# Top.net
KiCad netlist of a schematic drawn in Altium Designer
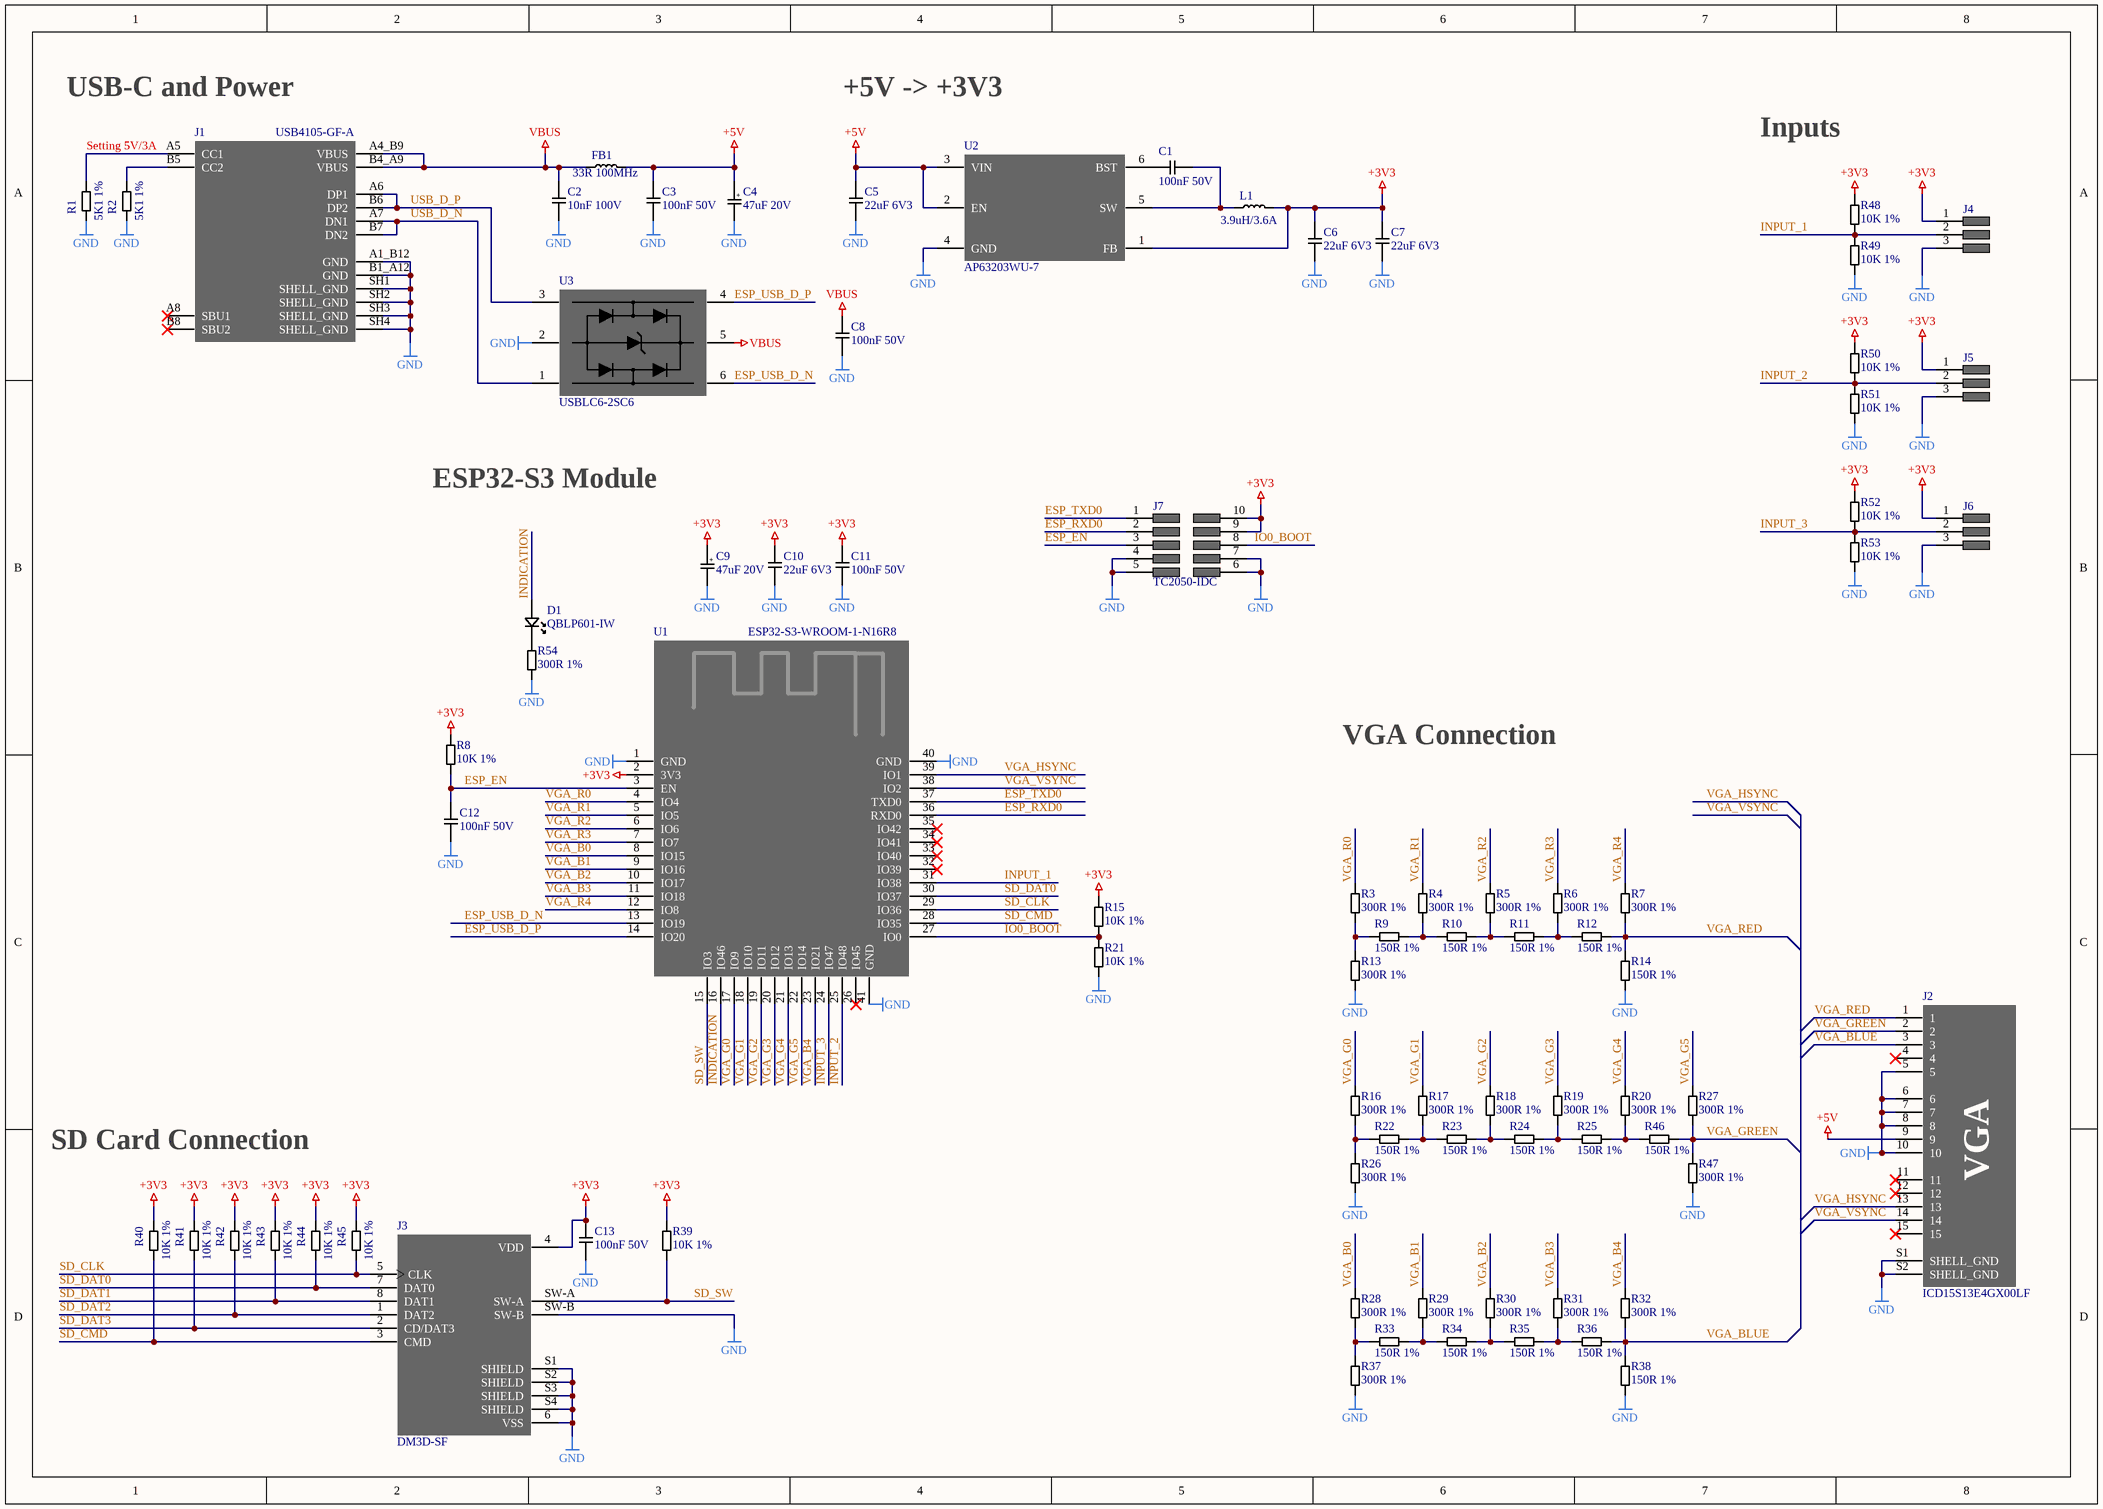
[diagram p0: Top.SchDoc]

(export (version "E")
  (design (tool "Eeschema 10.0.6"))
  (components
    (comp (ref "C1")
      (value "100nF 50V")
      (footprint "CAPC1608X06N")
      (description "0.1 µF ±10% 50V Ceramic Capacitor X7R 0603 (1608 Metric)")
      (fields (field (name "MPN") "GCM188R71H104KA57D"))
      (libsource (lib "VESA-ESP_LIB") (part "100nF 50V"))
    )
    (comp (ref "C2")
      (value "10nF 100V")
      (footprint "CAPC1608X06N")
      (description "10000 pF ±10% 100V Ceramic Capacitor X7R 0603 (1608 Metric)")
      (fields (field (name "MPN") "GCM188R72A103KA37D"))
      (libsource (lib "VESA-ESP_LIB") (part "10nF 100V"))
    )
    (comp (ref "C3")
      (value "100nF 50V")
      (footprint "CAPC1608X06N")
      (description "0.1 µF ±10% 50V Ceramic Capacitor X7R 0603 (1608 Metric)")
      (fields (field (name "MPN") "GCM188R71H104KA57D"))
      (libsource (lib "VESA-ESP_LIB") (part "100nF 50V"))
    )
    (comp (ref "C4")
      (value "47uF 20V")
      (footprint "865080342006")
      (description "47 µF 16 V Aluminum Electrolytic Capacitors Radial, Can - SMD 2000 Hrs @ 105°C")
      (libsource (lib "VESA-ESP_LIB") (part "47uF 20V"))
    )
    (comp (ref "C5")
      (value "22uF 6V3")
      (footprint "CAPC1608X06N")
      (description "22 µF ±20% 6.3V Ceramic Capacitor X5R 0603 (1608 Metric)")
      (fields (field (name "MPN") "GRM188R60J226MEA0D"))
      (libsource (lib "VESA-ESP_LIB") (part "22uF 6V3"))
    )
    (comp (ref "C6")
      (value "22uF 6V3")
      (footprint "CAPC1608X06N")
      (description "22 µF ±20% 6.3V Ceramic Capacitor X5R 0603 (1608 Metric)")
      (fields (field (name "MPN") "GRM188R60J226MEA0D"))
      (libsource (lib "VESA-ESP_LIB") (part "22uF 6V3"))
    )
    (comp (ref "C7")
      (value "22uF 6V3")
      (footprint "CAPC1608X06N")
      (description "22 µF ±20% 6.3V Ceramic Capacitor X5R 0603 (1608 Metric)")
      (fields (field (name "MPN") "GRM188R60J226MEA0D"))
      (libsource (lib "VESA-ESP_LIB") (part "22uF 6V3"))
    )
    (comp (ref "C8")
      (value "100nF 50V")
      (footprint "CAPC1608X06N")
      (description "0.1 µF ±10% 50V Ceramic Capacitor X7R 0603 (1608 Metric)")
      (fields (field (name "MPN") "GCM188R71H104KA57D"))
      (libsource (lib "VESA-ESP_LIB") (part "100nF 50V"))
    )
    (comp (ref "C9")
      (value "47uF 20V")
      (footprint "865080342006")
      (description "47 µF 16 V Aluminum Electrolytic Capacitors Radial, Can - SMD 2000 Hrs @ 105°C")
      (libsource (lib "VESA-ESP_LIB") (part "47uF 20V"))
    )
    (comp (ref "C10")
      (value "22uF 6V3")
      (footprint "CAPC1608X06N")
      (description "22 µF ±20% 6.3V Ceramic Capacitor X5R 0603 (1608 Metric)")
      (fields (field (name "MPN") "GRM188R60J226MEA0D"))
      (libsource (lib "VESA-ESP_LIB") (part "22uF 6V3"))
    )
    (comp (ref "C11")
      (value "100nF 50V")
      (footprint "CAPC1608X06N")
      (description "0.1 µF ±10% 50V Ceramic Capacitor X7R 0603 (1608 Metric)")
      (fields (field (name "MPN") "GCM188R71H104KA57D"))
      (libsource (lib "VESA-ESP_LIB") (part "100nF 50V"))
    )
    (comp (ref "C12")
      (value "100nF 50V")
      (footprint "CAPC1608X06N")
      (description "0.1 µF ±10% 50V Ceramic Capacitor X7R 0603 (1608 Metric)")
      (fields (field (name "MPN") "GCM188R71H104KA57D"))
      (libsource (lib "VESA-ESP_LIB") (part "100nF 50V"))
    )
    (comp (ref "C13")
      (value "100nF 50V")
      (footprint "CAPC1608X06N")
      (description "0.1 µF ±10% 50V Ceramic Capacitor X7R 0603 (1608 Metric)")
      (fields (field (name "MPN") "GCM188R71H104KA57D"))
      (libsource (lib "VESA-ESP_LIB") (part "100nF 50V"))
    )
    (comp (ref "D1")
      (value "QBLP601-IW")
      (footprint "LEDC1608X06N")
      (description "White LED Indication - Discrete 3.2V 0603 (1608 Metric)")
      (libsource (lib "VESA-ESP_LIB") (part "LED WHITE"))
    )
    (comp (ref "FB1")
      (value "33R 100MHz")
      (footprint "INDC1608X06N")
      (description "33 Ohms @ 100 MHz 1 Power Line Ferrite Bead 0603 (1608 Metric) 3A 25mOhm")
      (fields (field (name "MPN") "BLM18PG330SN1D"))
      (libsource (lib "VESA-ESP_LIB") (part "33R 100MHz"))
    )
    (comp (ref "J1")
      (value "USB4105-GF-A")
      (footprint "USB4105-GF-A")
      (libsource (lib "VESA-ESP_LIB") (part "USB4105-GF-A"))
    )
    (comp (ref "J2")
      (value "ICD15S13E4GX00LF")
      (footprint "ICD15S13E4GX00LF")
      (description "15 Position D-Sub, High Density Receptacle, Female Sockets Connector")
      (libsource (lib "VESA-ESP_LIB") (part "ICD15S13E4GX00LF"))
    )
    (comp (ref "J3")
      (value "DM3D-SF")
      (footprint "DM3D-SF")
      (description "10 (8 + 2) Position Card Connector Secure Digital - microSD™ Surface Mount, Right Angle Gold")
      (libsource (lib "VESA-ESP_LIB") (part "DM3D-SF"))
    )
    (comp (ref "J4")
      (value "Conn_2.54mm_3POS")
      (footprint "CONN_2.54MM_3POS")
      (libsource (lib "VESA-ESP_LIB") (part "Conn_2.54mm_3POS"))
    )
    (comp (ref "J5")
      (value "Conn_2.54mm_3POS")
      (footprint "CONN_2.54MM_3POS")
      (libsource (lib "VESA-ESP_LIB") (part "Conn_2.54mm_3POS"))
    )
    (comp (ref "J6")
      (value "Conn_2.54mm_3POS")
      (footprint "CONN_2.54MM_3POS")
      (libsource (lib "VESA-ESP_LIB") (part "Conn_2.54mm_3POS"))
    )
    (comp (ref "J7")
      (value "TC2050-IDC")
      (footprint "TAG_CONNECT")
      (libsource (lib "VESA-ESP_LIB") (part "TC2050-IDC"))
    )
    (comp (ref "L1")
      (value "3.9uH/3.6A")
      (footprint "SDE0604A-3R9M")
      (description "FIXED IND 3.9UH 3.6A 65 MOHM SMD")
      (fields (field (name "MPN") "SDE0604A-3R9M"))
      (libsource (lib "VESA-ESP_LIB") (part "3.9uH/3.6A"))
    )
    (comp (ref "R1")
      (value "5K1 1%")
      (footprint "RESC1608X06N")
      (description "5.1 kOhms ±1% 0.1W, 1/10W Chip Resistor 0603 (1608 Metric) Automotive AEC-Q200 Thick Film")
      (fields (field (name "MPN") "ERJ-3EKF5101V"))
      (libsource (lib "VESA-ESP_LIB") (part "5K1 1%"))
    )
    (comp (ref "R2")
      (value "5K1 1%")
      (footprint "RESC1608X06N")
      (description "5.1 kOhms ±1% 0.1W, 1/10W Chip Resistor 0603 (1608 Metric) Automotive AEC-Q200 Thick Film")
      (fields (field (name "MPN") "ERJ-3EKF5101V"))
      (libsource (lib "VESA-ESP_LIB") (part "5K1 1%"))
    )
    (comp (ref "R3")
      (value "300R 1%")
      (footprint "RESC1608X06N")
      (description "300 Ohms ±1% 0.1W, 1/10W Chip Resistor 0603 (1608 Metric) Automotive AEC-Q200 Thick Film")
      (fields (field (name "MPN") "ERJ-3EKF3000V"))
      (libsource (lib "VESA-ESP_LIB") (part "300R 1%"))
    )
    (comp (ref "R4")
      (value "300R 1%")
      (footprint "RESC1608X06N")
      (description "300 Ohms ±1% 0.1W, 1/10W Chip Resistor 0603 (1608 Metric) Automotive AEC-Q200 Thick Film")
      (fields (field (name "MPN") "ERJ-3EKF3000V"))
      (libsource (lib "VESA-ESP_LIB") (part "300R 1%"))
    )
    (comp (ref "R5")
      (value "300R 1%")
      (footprint "RESC1608X06N")
      (description "300 Ohms ±1% 0.1W, 1/10W Chip Resistor 0603 (1608 Metric) Automotive AEC-Q200 Thick Film")
      (fields (field (name "MPN") "ERJ-3EKF3000V"))
      (libsource (lib "VESA-ESP_LIB") (part "300R 1%"))
    )
    (comp (ref "R6")
      (value "300R 1%")
      (footprint "RESC1608X06N")
      (description "300 Ohms ±1% 0.1W, 1/10W Chip Resistor 0603 (1608 Metric) Automotive AEC-Q200 Thick Film")
      (fields (field (name "MPN") "ERJ-3EKF3000V"))
      (libsource (lib "VESA-ESP_LIB") (part "300R 1%"))
    )
    (comp (ref "R7")
      (value "300R 1%")
      (footprint "RESC1608X06N")
      (description "300 Ohms ±1% 0.1W, 1/10W Chip Resistor 0603 (1608 Metric) Automotive AEC-Q200 Thick Film")
      (fields (field (name "MPN") "ERJ-3EKF3000V"))
      (libsource (lib "VESA-ESP_LIB") (part "300R 1%"))
    )
    (comp (ref "R8")
      (value "10K 1%")
      (footprint "RESC1608X06N")
      (description "10 kOhms ±1% 0.1W, 1/10W Chip Resistor 0603 (1608 Metric) Automotive AEC-Q200 Thick Film")
      (fields (field (name "MPN") "ERJ-3EKF1002V"))
      (libsource (lib "VESA-ESP_LIB") (part "10K 1%"))
    )
    (comp (ref "R9")
      (value "150R 1%")
      (footprint "RESC1608X06N")
      (description "150 Ohms ±1% 0.1W, 1/10W Chip Resistor 0603 (1608 Metric) Automotive AEC-Q200 Thick Film")
      (fields (field (name "MPN") "ERJ-3EKF1500V"))
      (libsource (lib "VESA-ESP_LIB") (part "150R 1%"))
    )
    (comp (ref "R10")
      (value "150R 1%")
      (footprint "RESC1608X06N")
      (description "150 Ohms ±1% 0.1W, 1/10W Chip Resistor 0603 (1608 Metric) Automotive AEC-Q200 Thick Film")
      (fields (field (name "MPN") "ERJ-3EKF1500V"))
      (libsource (lib "VESA-ESP_LIB") (part "150R 1%"))
    )
    (comp (ref "R11")
      (value "150R 1%")
      (footprint "RESC1608X06N")
      (description "150 Ohms ±1% 0.1W, 1/10W Chip Resistor 0603 (1608 Metric) Automotive AEC-Q200 Thick Film")
      (fields (field (name "MPN") "ERJ-3EKF1500V"))
      (libsource (lib "VESA-ESP_LIB") (part "150R 1%"))
    )
    (comp (ref "R12")
      (value "150R 1%")
      (footprint "RESC1608X06N")
      (description "150 Ohms ±1% 0.1W, 1/10W Chip Resistor 0603 (1608 Metric) Automotive AEC-Q200 Thick Film")
      (fields (field (name "MPN") "ERJ-3EKF1500V"))
      (libsource (lib "VESA-ESP_LIB") (part "150R 1%"))
    )
    (comp (ref "R13")
      (value "300R 1%")
      (footprint "RESC1608X06N")
      (description "300 Ohms ±1% 0.1W, 1/10W Chip Resistor 0603 (1608 Metric) Automotive AEC-Q200 Thick Film")
      (fields (field (name "MPN") "ERJ-3EKF3000V"))
      (libsource (lib "VESA-ESP_LIB") (part "300R 1%"))
    )
    (comp (ref "R14")
      (value "150R 1%")
      (footprint "RESC1608X06N")
      (description "150 Ohms ±1% 0.1W, 1/10W Chip Resistor 0603 (1608 Metric) Automotive AEC-Q200 Thick Film")
      (fields (field (name "MPN") "ERJ-3EKF1500V"))
      (libsource (lib "VESA-ESP_LIB") (part "150R 1%"))
    )
    (comp (ref "R15")
      (value "10K 1%")
      (footprint "RESC1608X06N")
      (description "10 kOhms ±1% 0.1W, 1/10W Chip Resistor 0603 (1608 Metric) Automotive AEC-Q200 Thick Film")
      (fields (field (name "MPN") "ERJ-3EKF1002V"))
      (libsource (lib "VESA-ESP_LIB") (part "10K 1%"))
    )
    (comp (ref "R16")
      (value "300R 1%")
      (footprint "RESC1608X06N")
      (description "300 Ohms ±1% 0.1W, 1/10W Chip Resistor 0603 (1608 Metric) Automotive AEC-Q200 Thick Film")
      (fields (field (name "MPN") "ERJ-3EKF3000V"))
      (libsource (lib "VESA-ESP_LIB") (part "300R 1%"))
    )
    (comp (ref "R17")
      (value "300R 1%")
      (footprint "RESC1608X06N")
      (description "300 Ohms ±1% 0.1W, 1/10W Chip Resistor 0603 (1608 Metric) Automotive AEC-Q200 Thick Film")
      (fields (field (name "MPN") "ERJ-3EKF3000V"))
      (libsource (lib "VESA-ESP_LIB") (part "300R 1%"))
    )
    (comp (ref "R18")
      (value "300R 1%")
      (footprint "RESC1608X06N")
      (description "300 Ohms ±1% 0.1W, 1/10W Chip Resistor 0603 (1608 Metric) Automotive AEC-Q200 Thick Film")
      (fields (field (name "MPN") "ERJ-3EKF3000V"))
      (libsource (lib "VESA-ESP_LIB") (part "300R 1%"))
    )
    (comp (ref "R19")
      (value "300R 1%")
      (footprint "RESC1608X06N")
      (description "300 Ohms ±1% 0.1W, 1/10W Chip Resistor 0603 (1608 Metric) Automotive AEC-Q200 Thick Film")
      (fields (field (name "MPN") "ERJ-3EKF3000V"))
      (libsource (lib "VESA-ESP_LIB") (part "300R 1%"))
    )
    (comp (ref "R20")
      (value "300R 1%")
      (footprint "RESC1608X06N")
      (description "300 Ohms ±1% 0.1W, 1/10W Chip Resistor 0603 (1608 Metric) Automotive AEC-Q200 Thick Film")
      (fields (field (name "MPN") "ERJ-3EKF3000V"))
      (libsource (lib "VESA-ESP_LIB") (part "300R 1%"))
    )
    (comp (ref "R21")
      (value "10K 1%")
      (footprint "RESC1608X06N")
      (description "10 kOhms ±1% 0.1W, 1/10W Chip Resistor 0603 (1608 Metric) Automotive AEC-Q200 Thick Film")
      (fields (field (name "MPN") "ERJ-3EKF1002V"))
      (libsource (lib "VESA-ESP_LIB") (part "10K 1%"))
    )
    (comp (ref "R22")
      (value "150R 1%")
      (footprint "RESC1608X06N")
      (description "150 Ohms ±1% 0.1W, 1/10W Chip Resistor 0603 (1608 Metric) Automotive AEC-Q200 Thick Film")
      (fields (field (name "MPN") "ERJ-3EKF1500V"))
      (libsource (lib "VESA-ESP_LIB") (part "150R 1%"))
    )
    (comp (ref "R23")
      (value "150R 1%")
      (footprint "RESC1608X06N")
      (description "150 Ohms ±1% 0.1W, 1/10W Chip Resistor 0603 (1608 Metric) Automotive AEC-Q200 Thick Film")
      (fields (field (name "MPN") "ERJ-3EKF1500V"))
      (libsource (lib "VESA-ESP_LIB") (part "150R 1%"))
    )
    (comp (ref "R24")
      (value "150R 1%")
      (footprint "RESC1608X06N")
      (description "150 Ohms ±1% 0.1W, 1/10W Chip Resistor 0603 (1608 Metric) Automotive AEC-Q200 Thick Film")
      (fields (field (name "MPN") "ERJ-3EKF1500V"))
      (libsource (lib "VESA-ESP_LIB") (part "150R 1%"))
    )
    (comp (ref "R25")
      (value "150R 1%")
      (footprint "RESC1608X06N")
      (description "150 Ohms ±1% 0.1W, 1/10W Chip Resistor 0603 (1608 Metric) Automotive AEC-Q200 Thick Film")
      (fields (field (name "MPN") "ERJ-3EKF1500V"))
      (libsource (lib "VESA-ESP_LIB") (part "150R 1%"))
    )
    (comp (ref "R26")
      (value "300R 1%")
      (footprint "RESC1608X06N")
      (description "300 Ohms ±1% 0.1W, 1/10W Chip Resistor 0603 (1608 Metric) Automotive AEC-Q200 Thick Film")
      (fields (field (name "MPN") "ERJ-3EKF3000V"))
      (libsource (lib "VESA-ESP_LIB") (part "300R 1%"))
    )
    (comp (ref "R27")
      (value "300R 1%")
      (footprint "RESC1608X06N")
      (description "300 Ohms ±1% 0.1W, 1/10W Chip Resistor 0603 (1608 Metric) Automotive AEC-Q200 Thick Film")
      (fields (field (name "MPN") "ERJ-3EKF3000V"))
      (libsource (lib "VESA-ESP_LIB") (part "300R 1%"))
    )
    (comp (ref "R28")
      (value "300R 1%")
      (footprint "RESC1608X06N")
      (description "300 Ohms ±1% 0.1W, 1/10W Chip Resistor 0603 (1608 Metric) Automotive AEC-Q200 Thick Film")
      (fields (field (name "MPN") "ERJ-3EKF3000V"))
      (libsource (lib "VESA-ESP_LIB") (part "300R 1%"))
    )
    (comp (ref "R29")
      (value "300R 1%")
      (footprint "RESC1608X06N")
      (description "300 Ohms ±1% 0.1W, 1/10W Chip Resistor 0603 (1608 Metric) Automotive AEC-Q200 Thick Film")
      (fields (field (name "MPN") "ERJ-3EKF3000V"))
      (libsource (lib "VESA-ESP_LIB") (part "300R 1%"))
    )
    (comp (ref "R30")
      (value "300R 1%")
      (footprint "RESC1608X06N")
      (description "300 Ohms ±1% 0.1W, 1/10W Chip Resistor 0603 (1608 Metric) Automotive AEC-Q200 Thick Film")
      (fields (field (name "MPN") "ERJ-3EKF3000V"))
      (libsource (lib "VESA-ESP_LIB") (part "300R 1%"))
    )
    (comp (ref "R31")
      (value "300R 1%")
      (footprint "RESC1608X06N")
      (description "300 Ohms ±1% 0.1W, 1/10W Chip Resistor 0603 (1608 Metric) Automotive AEC-Q200 Thick Film")
      (fields (field (name "MPN") "ERJ-3EKF3000V"))
      (libsource (lib "VESA-ESP_LIB") (part "300R 1%"))
    )
    (comp (ref "R32")
      (value "300R 1%")
      (footprint "RESC1608X06N")
      (description "300 Ohms ±1% 0.1W, 1/10W Chip Resistor 0603 (1608 Metric) Automotive AEC-Q200 Thick Film")
      (fields (field (name "MPN") "ERJ-3EKF3000V"))
      (libsource (lib "VESA-ESP_LIB") (part "300R 1%"))
    )
    (comp (ref "R33")
      (value "150R 1%")
      (footprint "RESC1608X06N")
      (description "150 Ohms ±1% 0.1W, 1/10W Chip Resistor 0603 (1608 Metric) Automotive AEC-Q200 Thick Film")
      (fields (field (name "MPN") "ERJ-3EKF1500V"))
      (libsource (lib "VESA-ESP_LIB") (part "150R 1%"))
    )
    (comp (ref "R34")
      (value "150R 1%")
      (footprint "RESC1608X06N")
      (description "150 Ohms ±1% 0.1W, 1/10W Chip Resistor 0603 (1608 Metric) Automotive AEC-Q200 Thick Film")
      (fields (field (name "MPN") "ERJ-3EKF1500V"))
      (libsource (lib "VESA-ESP_LIB") (part "150R 1%"))
    )
    (comp (ref "R35")
      (value "150R 1%")
      (footprint "RESC1608X06N")
      (description "150 Ohms ±1% 0.1W, 1/10W Chip Resistor 0603 (1608 Metric) Automotive AEC-Q200 Thick Film")
      (fields (field (name "MPN") "ERJ-3EKF1500V"))
      (libsource (lib "VESA-ESP_LIB") (part "150R 1%"))
    )
    (comp (ref "R36")
      (value "150R 1%")
      (footprint "RESC1608X06N")
      (description "150 Ohms ±1% 0.1W, 1/10W Chip Resistor 0603 (1608 Metric) Automotive AEC-Q200 Thick Film")
      (fields (field (name "MPN") "ERJ-3EKF1500V"))
      (libsource (lib "VESA-ESP_LIB") (part "150R 1%"))
    )
    (comp (ref "R37")
      (value "300R 1%")
      (footprint "RESC1608X06N")
      (description "300 Ohms ±1% 0.1W, 1/10W Chip Resistor 0603 (1608 Metric) Automotive AEC-Q200 Thick Film")
      (fields (field (name "MPN") "ERJ-3EKF3000V"))
      (libsource (lib "VESA-ESP_LIB") (part "300R 1%"))
    )
    (comp (ref "R38")
      (value "150R 1%")
      (footprint "RESC1608X06N")
      (description "150 Ohms ±1% 0.1W, 1/10W Chip Resistor 0603 (1608 Metric) Automotive AEC-Q200 Thick Film")
      (fields (field (name "MPN") "ERJ-3EKF1500V"))
      (libsource (lib "VESA-ESP_LIB") (part "150R 1%"))
    )
    (comp (ref "R39")
      (value "10K 1%")
      (footprint "RESC1608X06N")
      (description "10 kOhms ±1% 0.1W, 1/10W Chip Resistor 0603 (1608 Metric) Automotive AEC-Q200 Thick Film")
      (fields (field (name "MPN") "ERJ-3EKF1002V"))
      (libsource (lib "VESA-ESP_LIB") (part "10K 1%"))
    )
    (comp (ref "R40")
      (value "10K 1%")
      (footprint "RESC1608X06N")
      (description "10 kOhms ±1% 0.1W, 1/10W Chip Resistor 0603 (1608 Metric) Automotive AEC-Q200 Thick Film")
      (fields (field (name "MPN") "ERJ-3EKF1002V"))
      (libsource (lib "VESA-ESP_LIB") (part "10K 1%"))
    )
    (comp (ref "R41")
      (value "10K 1%")
      (footprint "RESC1608X06N")
      (description "10 kOhms ±1% 0.1W, 1/10W Chip Resistor 0603 (1608 Metric) Automotive AEC-Q200 Thick Film")
      (fields (field (name "MPN") "ERJ-3EKF1002V"))
      (libsource (lib "VESA-ESP_LIB") (part "10K 1%"))
    )
    (comp (ref "R42")
      (value "10K 1%")
      (footprint "RESC1608X06N")
      (description "10 kOhms ±1% 0.1W, 1/10W Chip Resistor 0603 (1608 Metric) Automotive AEC-Q200 Thick Film")
      (fields (field (name "MPN") "ERJ-3EKF1002V"))
      (libsource (lib "VESA-ESP_LIB") (part "10K 1%"))
    )
    (comp (ref "R43")
      (value "10K 1%")
      (footprint "RESC1608X06N")
      (description "10 kOhms ±1% 0.1W, 1/10W Chip Resistor 0603 (1608 Metric) Automotive AEC-Q200 Thick Film")
      (fields (field (name "MPN") "ERJ-3EKF1002V"))
      (libsource (lib "VESA-ESP_LIB") (part "10K 1%"))
    )
    (comp (ref "R44")
      (value "10K 1%")
      (footprint "RESC1608X06N")
      (description "10 kOhms ±1% 0.1W, 1/10W Chip Resistor 0603 (1608 Metric) Automotive AEC-Q200 Thick Film")
      (fields (field (name "MPN") "ERJ-3EKF1002V"))
      (libsource (lib "VESA-ESP_LIB") (part "10K 1%"))
    )
    (comp (ref "R45")
      (value "10K 1%")
      (footprint "RESC1608X06N")
      (description "10 kOhms ±1% 0.1W, 1/10W Chip Resistor 0603 (1608 Metric) Automotive AEC-Q200 Thick Film")
      (fields (field (name "MPN") "ERJ-3EKF1002V"))
      (libsource (lib "VESA-ESP_LIB") (part "10K 1%"))
    )
    (comp (ref "R46")
      (value "150R 1%")
      (footprint "RESC1608X06N")
      (description "150 Ohms ±1% 0.1W, 1/10W Chip Resistor 0603 (1608 Metric) Automotive AEC-Q200 Thick Film")
      (fields (field (name "MPN") "ERJ-3EKF1500V"))
      (libsource (lib "VESA-ESP_LIB") (part "150R 1%"))
    )
    (comp (ref "R47")
      (value "300R 1%")
      (footprint "RESC1608X06N")
      (description "300 Ohms ±1% 0.1W, 1/10W Chip Resistor 0603 (1608 Metric) Automotive AEC-Q200 Thick Film")
      (fields (field (name "MPN") "ERJ-3EKF3000V"))
      (libsource (lib "VESA-ESP_LIB") (part "300R 1%"))
    )
    (comp (ref "R48")
      (value "10K 1%")
      (footprint "RESC1608X06N")
      (description "10 kOhms ±1% 0.1W, 1/10W Chip Resistor 0603 (1608 Metric) Automotive AEC-Q200 Thick Film")
      (fields (field (name "MPN") "ERJ-3EKF1002V"))
      (libsource (lib "VESA-ESP_LIB") (part "10K 1%"))
    )
    (comp (ref "R49")
      (value "10K 1%")
      (footprint "RESC1608X06N")
      (description "10 kOhms ±1% 0.1W, 1/10W Chip Resistor 0603 (1608 Metric) Automotive AEC-Q200 Thick Film")
      (fields (field (name "MPN") "ERJ-3EKF1002V"))
      (libsource (lib "VESA-ESP_LIB") (part "10K 1%"))
    )
    (comp (ref "R50")
      (value "10K 1%")
      (footprint "RESC1608X06N")
      (description "10 kOhms ±1% 0.1W, 1/10W Chip Resistor 0603 (1608 Metric) Automotive AEC-Q200 Thick Film")
      (fields (field (name "MPN") "ERJ-3EKF1002V"))
      (libsource (lib "VESA-ESP_LIB") (part "10K 1%"))
    )
    (comp (ref "R51")
      (value "10K 1%")
      (footprint "RESC1608X06N")
      (description "10 kOhms ±1% 0.1W, 1/10W Chip Resistor 0603 (1608 Metric) Automotive AEC-Q200 Thick Film")
      (fields (field (name "MPN") "ERJ-3EKF1002V"))
      (libsource (lib "VESA-ESP_LIB") (part "10K 1%"))
    )
    (comp (ref "R52")
      (value "10K 1%")
      (footprint "RESC1608X06N")
      (description "10 kOhms ±1% 0.1W, 1/10W Chip Resistor 0603 (1608 Metric) Automotive AEC-Q200 Thick Film")
      (fields (field (name "MPN") "ERJ-3EKF1002V"))
      (libsource (lib "VESA-ESP_LIB") (part "10K 1%"))
    )
    (comp (ref "R53")
      (value "10K 1%")
      (footprint "RESC1608X06N")
      (description "10 kOhms ±1% 0.1W, 1/10W Chip Resistor 0603 (1608 Metric) Automotive AEC-Q200 Thick Film")
      (fields (field (name "MPN") "ERJ-3EKF1002V"))
      (libsource (lib "VESA-ESP_LIB") (part "10K 1%"))
    )
    (comp (ref "R54")
      (value "300R 1%")
      (footprint "RESC1608X06N")
      (description "300 Ohms ±1% 0.1W, 1/10W Chip Resistor 0603 (1608 Metric) Automotive AEC-Q200 Thick Film")
      (fields (field (name "MPN") "ERJ-3EKF3000V"))
      (libsource (lib "VESA-ESP_LIB") (part "300R 1%"))
    )
    (comp (ref "U1")
      (value "ESP32-S3-WROOM-1-N16R8")
      (footprint "ESP32-S3-WROOM")
      (description "Bluetooth, WiFi 802.11b/g/n, Bluetooth v5.0 Transceiver Module 2.4GHz PCB Trace Surface Mount")
      (libsource (lib "VESA-ESP_LIB") (part "ESP32-S3-WROOM-1-N16R8"))
    )
    (comp (ref "U2")
      (value "AP63203WU-7")
      (footprint "SOT95P245X100-6N")
      (description "Buck Switching Regulator IC Positive Fixed 3.3V 1 Output 2A SOT-23-6 Thin, TSOT-23-6")
      (libsource (lib "VESA-ESP_LIB") (part "AP63203WU-7"))
    )
    (comp (ref "U3")
      (value "USBLC6-2SC6")
      (footprint "SOT95P245X100-6N")
      (description "17V Clamp 5A (8/20µs) Ipp Tvs Diode Surface Mount SOT-23-6")
      (libsource (lib "VESA-ESP_LIB") (part "USBLC6-2SC6"))
    )
  )
  (nets
    (net (code "1") (name "+3V3") (class "Default")
      (node (ref "C10") (pin "2") (pinfunction "2_2") (pintype "passive"))
      (node (ref "C11") (pin "2") (pinfunction "2_2") (pintype "passive"))
      (node (ref "C13") (pin "2") (pinfunction "2_2") (pintype "passive"))
      (node (ref "C6") (pin "2") (pinfunction "2_2") (pintype "passive"))
      (node (ref "C7") (pin "2") (pinfunction "2_2") (pintype "passive"))
      (node (ref "C9") (pin "1") (pinfunction "1_1") (pintype "passive"))
      (node (ref "J3") (pin "4") (pinfunction "VDD_4") (pintype "passive"))
      (node (ref "J4") (pin "1") (pinfunction "1_1") (pintype "passive"))
      (node (ref "J5") (pin "1") (pinfunction "1_1") (pintype "passive"))
      (node (ref "J6") (pin "1") (pinfunction "1_1") (pintype "passive"))
      (node (ref "J7") (pin "10") (pinfunction "10_10") (pintype "passive"))
      (node (ref "J7") (pin "9") (pinfunction "9_9") (pintype "passive"))
      (node (ref "L1") (pin "2") (pinfunction "2_2") (pintype "passive"))
      (node (ref "R15") (pin "1") (pinfunction "1_1") (pintype "passive"))
      (node (ref "R39") (pin "1") (pinfunction "1_1") (pintype "passive"))
      (node (ref "R40") (pin "1") (pinfunction "1_1") (pintype "passive"))
      (node (ref "R41") (pin "1") (pinfunction "1_1") (pintype "passive"))
      (node (ref "R42") (pin "1") (pinfunction "1_1") (pintype "passive"))
      (node (ref "R43") (pin "1") (pinfunction "1_1") (pintype "passive"))
      (node (ref "R44") (pin "1") (pinfunction "1_1") (pintype "passive"))
      (node (ref "R45") (pin "1") (pinfunction "1_1") (pintype "passive"))
      (node (ref "R48") (pin "1") (pinfunction "1_1") (pintype "passive"))
      (node (ref "R50") (pin "1") (pinfunction "1_1") (pintype "passive"))
      (node (ref "R52") (pin "1") (pinfunction "1_1") (pintype "passive"))
      (node (ref "R8") (pin "1") (pinfunction "1_1") (pintype "passive"))
      (node (ref "U1") (pin "2") (pinfunction "3V3_2") (pintype "passive"))
      (node (ref "U2") (pin "1") (pinfunction "FB_1") (pintype "passive"))
    )
    (net (code "2") (name "+5V") (class "Default")
      (node (ref "C3") (pin "2") (pinfunction "2_2") (pintype "passive"))
      (node (ref "C4") (pin "1") (pinfunction "1_1") (pintype "passive"))
      (node (ref "C5") (pin "2") (pinfunction "2_2") (pintype "passive"))
      (node (ref "FB1") (pin "2") (pinfunction "2_2") (pintype "passive"))
      (node (ref "J2") (pin "9") (pinfunction "9_9") (pintype "passive"))
      (node (ref "U2") (pin "2") (pinfunction "EN_2") (pintype "passive"))
      (node (ref "U2") (pin "3") (pinfunction "VIN_3") (pintype "passive"))
    )
    (net (code "3") (name "/ESP_EN") (class "Default")
      (node (ref "C12") (pin "2") (pinfunction "2_2") (pintype "passive"))
      (node (ref "J7") (pin "3") (pinfunction "3_3") (pintype "passive"))
      (node (ref "R8") (pin "2") (pinfunction "2_2") (pintype "passive"))
      (node (ref "U1") (pin "3") (pinfunction "EN_3") (pintype "passive"))
    )
    (net (code "4") (name "/ESP_RXD0") (class "Default")
      (node (ref "J7") (pin "2") (pinfunction "2_2") (pintype "passive"))
      (node (ref "U1") (pin "36") (pinfunction "RXD0_36") (pintype "passive"))
    )
    (net (code "5") (name "/ESP_TXD0") (class "Default")
      (node (ref "J7") (pin "1") (pinfunction "1_1") (pintype "passive"))
      (node (ref "U1") (pin "37") (pinfunction "TXD0_37") (pintype "passive"))
    )
    (net (code "6") (name "/ESP_USB_D_N") (class "Default")
      (node (ref "U1") (pin "13") (pinfunction "IO19_13") (pintype "passive"))
      (node (ref "U3") (pin "6") (pinfunction "6_6") (pintype "passive"))
    )
    (net (code "7") (name "/ESP_USB_D_P") (class "Default")
      (node (ref "U1") (pin "14") (pinfunction "IO20_14") (pintype "passive"))
      (node (ref "U3") (pin "4") (pinfunction "4_4") (pintype "passive"))
    )
    (net (code "8") (name "/INDICATION") (class "Default")
      (node (ref "D1") (pin "1") (pinfunction "1_1") (pintype "passive"))
      (node (ref "U1") (pin "16") (pinfunction "IO46_16") (pintype "passive"))
    )
    (net (code "9") (name "/INPUT_1") (class "Default")
      (node (ref "J4") (pin "2") (pinfunction "2_2") (pintype "passive"))
      (node (ref "R48") (pin "2") (pinfunction "2_2") (pintype "passive"))
      (node (ref "R49") (pin "1") (pinfunction "1_1") (pintype "passive"))
      (node (ref "U1") (pin "31") (pinfunction "IO38_31") (pintype "passive"))
    )
    (net (code "10") (name "/INPUT_2") (class "Default")
      (node (ref "J5") (pin "2") (pinfunction "2_2") (pintype "passive"))
      (node (ref "R50") (pin "2") (pinfunction "2_2") (pintype "passive"))
      (node (ref "R51") (pin "1") (pinfunction "1_1") (pintype "passive"))
      (node (ref "U1") (pin "25") (pinfunction "IO48_25") (pintype "passive"))
    )
    (net (code "11") (name "/INPUT_3") (class "Default")
      (node (ref "J6") (pin "2") (pinfunction "2_2") (pintype "passive"))
      (node (ref "R52") (pin "2") (pinfunction "2_2") (pintype "passive"))
      (node (ref "R53") (pin "1") (pinfunction "1_1") (pintype "passive"))
      (node (ref "U1") (pin "24") (pinfunction "IO47_24") (pintype "passive"))
    )
    (net (code "12") (name "/IO0_BOOT") (class "Default")
      (node (ref "J7") (pin "8") (pinfunction "8_8") (pintype "passive"))
      (node (ref "R15") (pin "2") (pinfunction "2_2") (pintype "passive"))
      (node (ref "R21") (pin "1") (pinfunction "1_1") (pintype "passive"))
      (node (ref "U1") (pin "27") (pinfunction "IO0_27") (pintype "passive"))
    )
    (net (code "13") (name "/SD_CLK") (class "Default")
      (node (ref "J3") (pin "5") (pinfunction "CLK_5") (pintype "passive"))
      (node (ref "R45") (pin "2") (pinfunction "2_2") (pintype "passive"))
      (node (ref "U1") (pin "29") (pinfunction "IO36_29") (pintype "passive"))
    )
    (net (code "14") (name "/SD_CMD") (class "Default")
      (node (ref "J3") (pin "3") (pinfunction "CMD_3") (pintype "passive"))
      (node (ref "R40") (pin "2") (pinfunction "2_2") (pintype "passive"))
      (node (ref "U1") (pin "28") (pinfunction "IO35_28") (pintype "passive"))
    )
    (net (code "15") (name "/SD_DAT0") (class "Default")
      (node (ref "J3") (pin "7") (pinfunction "DAT0_7") (pintype "passive"))
      (node (ref "R44") (pin "2") (pinfunction "2_2") (pintype "passive"))
      (node (ref "U1") (pin "30") (pinfunction "IO37_30") (pintype "passive"))
    )
    (net (code "16") (name "/SD_DAT1") (class "Default")
      (node (ref "J3") (pin "8") (pinfunction "DAT1_8") (pintype "passive"))
      (node (ref "R43") (pin "2") (pinfunction "2_2") (pintype "passive"))
    )
    (net (code "17") (name "/SD_DAT2") (class "Default")
      (node (ref "J3") (pin "1") (pinfunction "DAT2_1") (pintype "passive"))
      (node (ref "R42") (pin "2") (pinfunction "2_2") (pintype "passive"))
    )
    (net (code "18") (name "/SD_DAT3") (class "Default")
      (node (ref "J3") (pin "2") (pinfunction "CD/DAT3_2") (pintype "passive"))
      (node (ref "R41") (pin "2") (pinfunction "2_2") (pintype "passive"))
    )
    (net (code "19") (name "/SD_SW") (class "Default")
      (node (ref "J3") (pin "SW-A") (pinfunction "SW-A_SW-A") (pintype "passive"))
      (node (ref "R39") (pin "2") (pinfunction "2_2") (pintype "passive"))
      (node (ref "U1") (pin "15") (pinfunction "IO3_15") (pintype "passive"))
    )
    (net (code "20") (name "/USB_D_N") (class "Default")
      (node (ref "J1") (pin "A7") (pinfunction "DN1_A7") (pintype "passive"))
      (node (ref "J1") (pin "B7") (pinfunction "DN2_B7") (pintype "passive"))
      (node (ref "U3") (pin "1") (pinfunction "1_1") (pintype "passive"))
    )
    (net (code "21") (name "/USB_D_P") (class "Default")
      (node (ref "J1") (pin "A6") (pinfunction "DP1_A6") (pintype "passive"))
      (node (ref "J1") (pin "B6") (pinfunction "DP2_B6") (pintype "passive"))
      (node (ref "U3") (pin "3") (pinfunction "3_3") (pintype "passive"))
    )
    (net (code "22") (name "/VGA_B0") (class "Default")
      (node (ref "R28") (pin "1") (pinfunction "1_1") (pintype "passive"))
      (node (ref "U1") (pin "8") (pinfunction "IO15_8") (pintype "passive"))
    )
    (net (code "23") (name "/VGA_B1") (class "Default")
      (node (ref "R29") (pin "1") (pinfunction "1_1") (pintype "passive"))
      (node (ref "U1") (pin "9") (pinfunction "IO16_9") (pintype "passive"))
    )
    (net (code "24") (name "/VGA_B2") (class "Default")
      (node (ref "R30") (pin "1") (pinfunction "1_1") (pintype "passive"))
      (node (ref "U1") (pin "10") (pinfunction "IO17_10") (pintype "passive"))
    )
    (net (code "25") (name "/VGA_B3") (class "Default")
      (node (ref "R31") (pin "1") (pinfunction "1_1") (pintype "passive"))
      (node (ref "U1") (pin "11") (pinfunction "IO18_11") (pintype "passive"))
    )
    (net (code "26") (name "/VGA_B4") (class "Default")
      (node (ref "R32") (pin "1") (pinfunction "1_1") (pintype "passive"))
      (node (ref "U1") (pin "23") (pinfunction "IO21_23") (pintype "passive"))
    )
    (net (code "27") (name "/VGA_BLUE") (class "Default")
      (node (ref "J2") (pin "3") (pinfunction "3_3") (pintype "passive"))
      (node (ref "R32") (pin "2") (pinfunction "2_2") (pintype "passive"))
      (node (ref "R36") (pin "2") (pinfunction "2_2") (pintype "passive"))
      (node (ref "R38") (pin "1") (pinfunction "1_1") (pintype "passive"))
    )
    (net (code "28") (name "/VGA_G0") (class "Default")
      (node (ref "R16") (pin "1") (pinfunction "1_1") (pintype "passive"))
      (node (ref "U1") (pin "17") (pinfunction "IO9_17") (pintype "passive"))
    )
    (net (code "29") (name "/VGA_G1") (class "Default")
      (node (ref "R17") (pin "1") (pinfunction "1_1") (pintype "passive"))
      (node (ref "U1") (pin "18") (pinfunction "IO10_18") (pintype "passive"))
    )
    (net (code "30") (name "/VGA_G2") (class "Default")
      (node (ref "R18") (pin "1") (pinfunction "1_1") (pintype "passive"))
      (node (ref "U1") (pin "19") (pinfunction "IO11_19") (pintype "passive"))
    )
    (net (code "31") (name "/VGA_G3") (class "Default")
      (node (ref "R19") (pin "1") (pinfunction "1_1") (pintype "passive"))
      (node (ref "U1") (pin "20") (pinfunction "IO12_20") (pintype "passive"))
    )
    (net (code "32") (name "/VGA_G4") (class "Default")
      (node (ref "R20") (pin "1") (pinfunction "1_1") (pintype "passive"))
      (node (ref "U1") (pin "21") (pinfunction "IO13_21") (pintype "passive"))
    )
    (net (code "33") (name "/VGA_G5") (class "Default")
      (node (ref "R27") (pin "1") (pinfunction "1_1") (pintype "passive"))
      (node (ref "U1") (pin "22") (pinfunction "IO14_22") (pintype "passive"))
    )
    (net (code "34") (name "/VGA_GREEN") (class "Default")
      (node (ref "J2") (pin "2") (pinfunction "2_2") (pintype "passive"))
      (node (ref "R27") (pin "2") (pinfunction "2_2") (pintype "passive"))
      (node (ref "R46") (pin "2") (pinfunction "2_2") (pintype "passive"))
      (node (ref "R47") (pin "2") (pinfunction "2_2") (pintype "passive"))
    )
    (net (code "35") (name "/VGA_HSYNC") (class "Default")
      (node (ref "J2") (pin "13") (pinfunction "13_13") (pintype "passive"))
      (node (ref "U1") (pin "39") (pinfunction "IO1_39") (pintype "passive"))
    )
    (net (code "36") (name "/VGA_R0") (class "Default")
      (node (ref "R3") (pin "1") (pinfunction "1_1") (pintype "passive"))
      (node (ref "U1") (pin "4") (pinfunction "IO4_4") (pintype "passive"))
    )
    (net (code "37") (name "/VGA_R1") (class "Default")
      (node (ref "R4") (pin "1") (pinfunction "1_1") (pintype "passive"))
      (node (ref "U1") (pin "5") (pinfunction "IO5_5") (pintype "passive"))
    )
    (net (code "38") (name "/VGA_R2") (class "Default")
      (node (ref "R5") (pin "1") (pinfunction "1_1") (pintype "passive"))
      (node (ref "U1") (pin "6") (pinfunction "IO6_6") (pintype "passive"))
    )
    (net (code "39") (name "/VGA_R3") (class "Default")
      (node (ref "R6") (pin "1") (pinfunction "1_1") (pintype "passive"))
      (node (ref "U1") (pin "7") (pinfunction "IO7_7") (pintype "passive"))
    )
    (net (code "40") (name "/VGA_R4") (class "Default")
      (node (ref "R7") (pin "1") (pinfunction "1_1") (pintype "passive"))
      (node (ref "U1") (pin "12") (pinfunction "IO8_12") (pintype "passive"))
    )
    (net (code "41") (name "/VGA_RED") (class "Default")
      (node (ref "J2") (pin "1") (pinfunction "1_1") (pintype "passive"))
      (node (ref "R12") (pin "2") (pinfunction "2_2") (pintype "passive"))
      (node (ref "R14") (pin "1") (pinfunction "1_1") (pintype "passive"))
      (node (ref "R7") (pin "2") (pinfunction "2_2") (pintype "passive"))
    )
    (net (code "42") (name "/VGA_VSYNC") (class "Default")
      (node (ref "J2") (pin "14") (pinfunction "14_14") (pintype "passive"))
      (node (ref "U1") (pin "38") (pinfunction "IO2_38") (pintype "passive"))
    )
    (net (code "43") (name "GND") (class "Default")
      (node (ref "C10") (pin "1") (pinfunction "1_1") (pintype "passive"))
      (node (ref "C11") (pin "1") (pinfunction "1_1") (pintype "passive"))
      (node (ref "C12") (pin "1") (pinfunction "1_1") (pintype "passive"))
      (node (ref "C13") (pin "1") (pinfunction "1_1") (pintype "passive"))
      (node (ref "C2") (pin "1") (pinfunction "1_1") (pintype "passive"))
      (node (ref "C3") (pin "1") (pinfunction "1_1") (pintype "passive"))
      (node (ref "C4") (pin "2") (pinfunction "2_2") (pintype "passive"))
      (node (ref "C5") (pin "1") (pinfunction "1_1") (pintype "passive"))
      (node (ref "C6") (pin "1") (pinfunction "1_1") (pintype "passive"))
      (node (ref "C7") (pin "1") (pinfunction "1_1") (pintype "passive"))
      (node (ref "C8") (pin "1") (pinfunction "1_1") (pintype "passive"))
      (node (ref "C9") (pin "2") (pinfunction "2_2") (pintype "passive"))
      (node (ref "J1") (pin "A1_B12") (pinfunction "GND_A1_B12") (pintype "passive"))
      (node (ref "J1") (pin "B1_A12") (pinfunction "GND_B1_A12") (pintype "passive"))
      (node (ref "J1") (pin "SH1") (pinfunction "SHELL_GND_SH1") (pintype "passive"))
      (node (ref "J1") (pin "SH2") (pinfunction "SHELL_GND_SH2") (pintype "passive"))
      (node (ref "J1") (pin "SH3") (pinfunction "SHELL_GND_SH3") (pintype "passive"))
      (node (ref "J1") (pin "SH4") (pinfunction "SHELL_GND_SH4") (pintype "passive"))
      (node (ref "J2") (pin "10") (pinfunction "10_10") (pintype "passive"))
      (node (ref "J2") (pin "5") (pinfunction "5_5") (pintype "passive"))
      (node (ref "J2") (pin "6") (pinfunction "6_6") (pintype "passive"))
      (node (ref "J2") (pin "7") (pinfunction "7_7") (pintype "passive"))
      (node (ref "J2") (pin "8") (pinfunction "8_8") (pintype "passive"))
      (node (ref "J2") (pin "S1") (pinfunction "SHELL_GND_S1") (pintype "passive"))
      (node (ref "J2") (pin "S2") (pinfunction "SHELL_GND_S2") (pintype "passive"))
      (node (ref "J3") (pin "6") (pinfunction "VSS_6") (pintype "passive"))
      (node (ref "J3") (pin "S1") (pinfunction "SHIELD_S1") (pintype "passive"))
      (node (ref "J3") (pin "S2") (pinfunction "SHIELD_S2") (pintype "passive"))
      (node (ref "J3") (pin "S3") (pinfunction "SHIELD_S3") (pintype "passive"))
      (node (ref "J3") (pin "S4") (pinfunction "SHIELD_S4") (pintype "passive"))
      (node (ref "J3") (pin "SW-B") (pinfunction "SW-B_SW-B") (pintype "passive"))
      (node (ref "J4") (pin "3") (pinfunction "3_3") (pintype "passive"))
      (node (ref "J5") (pin "3") (pinfunction "3_3") (pintype "passive"))
      (node (ref "J6") (pin "3") (pinfunction "3_3") (pintype "passive"))
      (node (ref "J7") (pin "4") (pinfunction "4_4") (pintype "passive"))
      (node (ref "J7") (pin "5") (pinfunction "5_5") (pintype "passive"))
      (node (ref "J7") (pin "6") (pinfunction "6_6") (pintype "passive"))
      (node (ref "J7") (pin "7") (pinfunction "7_7") (pintype "passive"))
      (node (ref "R1") (pin "1") (pinfunction "1_1") (pintype "passive"))
      (node (ref "R13") (pin "1") (pinfunction "1_1") (pintype "passive"))
      (node (ref "R14") (pin "2") (pinfunction "2_2") (pintype "passive"))
      (node (ref "R2") (pin "1") (pinfunction "1_1") (pintype "passive"))
      (node (ref "R21") (pin "2") (pinfunction "2_2") (pintype "passive"))
      (node (ref "R26") (pin "1") (pinfunction "1_1") (pintype "passive"))
      (node (ref "R37") (pin "1") (pinfunction "1_1") (pintype "passive"))
      (node (ref "R38") (pin "2") (pinfunction "2_2") (pintype "passive"))
      (node (ref "R47") (pin "1") (pinfunction "1_1") (pintype "passive"))
      (node (ref "R49") (pin "2") (pinfunction "2_2") (pintype "passive"))
      (node (ref "R51") (pin "2") (pinfunction "2_2") (pintype "passive"))
      (node (ref "R53") (pin "2") (pinfunction "2_2") (pintype "passive"))
      (node (ref "R54") (pin "1") (pinfunction "1_1") (pintype "passive"))
      (node (ref "U1") (pin "1") (pinfunction "GND_1") (pintype "passive"))
      (node (ref "U1") (pin "40") (pinfunction "GND_40") (pintype "passive"))
      (node (ref "U1") (pin "41") (pinfunction "GND_41") (pintype "passive"))
      (node (ref "U2") (pin "4") (pinfunction "GND_4") (pintype "passive"))
      (node (ref "U3") (pin "2") (pinfunction "2_2") (pintype "passive"))
    )
    (net (code "44") (name "Net-(D1-Pad2)") (class "Default")
      (node (ref "D1") (pin "2") (pinfunction "2_2") (pintype "passive"))
      (node (ref "R54") (pin "2") (pinfunction "2_2") (pintype "passive"))
    )
    (net (code "45") (name "Net-(J1-CC1)") (class "Default")
      (node (ref "J1") (pin "A5") (pinfunction "CC1_A5") (pintype "passive"))
      (node (ref "R1") (pin "2") (pinfunction "2_2") (pintype "passive"))
    )
    (net (code "46") (name "Net-(J1-CC2)") (class "Default")
      (node (ref "J1") (pin "B5") (pinfunction "CC2_B5") (pintype "passive"))
      (node (ref "R2") (pin "2") (pinfunction "2_2") (pintype "passive"))
    )
    (net (code "47") (name "Net-(R10-Pad1)") (class "Default")
      (node (ref "R10") (pin "1") (pinfunction "1_1") (pintype "passive"))
      (node (ref "R4") (pin "2") (pinfunction "2_2") (pintype "passive"))
      (node (ref "R9") (pin "2") (pinfunction "2_2") (pintype "passive"))
    )
    (net (code "48") (name "Net-(R10-Pad2)") (class "Default")
      (node (ref "R10") (pin "2") (pinfunction "2_2") (pintype "passive"))
      (node (ref "R11") (pin "1") (pinfunction "1_1") (pintype "passive"))
      (node (ref "R5") (pin "2") (pinfunction "2_2") (pintype "passive"))
    )
    (net (code "49") (name "Net-(R11-Pad2)") (class "Default")
      (node (ref "R11") (pin "2") (pinfunction "2_2") (pintype "passive"))
      (node (ref "R12") (pin "1") (pinfunction "1_1") (pintype "passive"))
      (node (ref "R6") (pin "2") (pinfunction "2_2") (pintype "passive"))
    )
    (net (code "50") (name "Net-(R13-Pad2)") (class "Default")
      (node (ref "R13") (pin "2") (pinfunction "2_2") (pintype "passive"))
      (node (ref "R3") (pin "2") (pinfunction "2_2") (pintype "passive"))
      (node (ref "R9") (pin "1") (pinfunction "1_1") (pintype "passive"))
    )
    (net (code "51") (name "Net-(R16-Pad2)") (class "Default")
      (node (ref "R16") (pin "2") (pinfunction "2_2") (pintype "passive"))
      (node (ref "R22") (pin "1") (pinfunction "1_1") (pintype "passive"))
      (node (ref "R26") (pin "2") (pinfunction "2_2") (pintype "passive"))
    )
    (net (code "52") (name "Net-(R17-Pad2)") (class "Default")
      (node (ref "R17") (pin "2") (pinfunction "2_2") (pintype "passive"))
      (node (ref "R22") (pin "2") (pinfunction "2_2") (pintype "passive"))
      (node (ref "R23") (pin "1") (pinfunction "1_1") (pintype "passive"))
    )
    (net (code "53") (name "Net-(R18-Pad2)") (class "Default")
      (node (ref "R18") (pin "2") (pinfunction "2_2") (pintype "passive"))
      (node (ref "R23") (pin "2") (pinfunction "2_2") (pintype "passive"))
      (node (ref "R24") (pin "1") (pinfunction "1_1") (pintype "passive"))
    )
    (net (code "54") (name "Net-(R19-Pad2)") (class "Default")
      (node (ref "R19") (pin "2") (pinfunction "2_2") (pintype "passive"))
      (node (ref "R24") (pin "2") (pinfunction "2_2") (pintype "passive"))
      (node (ref "R25") (pin "1") (pinfunction "1_1") (pintype "passive"))
    )
    (net (code "55") (name "Net-(R20-Pad2)") (class "Default")
      (node (ref "R20") (pin "2") (pinfunction "2_2") (pintype "passive"))
      (node (ref "R25") (pin "2") (pinfunction "2_2") (pintype "passive"))
      (node (ref "R46") (pin "1") (pinfunction "1_1") (pintype "passive"))
    )
    (net (code "56") (name "Net-(R28-Pad2)") (class "Default")
      (node (ref "R28") (pin "2") (pinfunction "2_2") (pintype "passive"))
      (node (ref "R33") (pin "1") (pinfunction "1_1") (pintype "passive"))
      (node (ref "R37") (pin "2") (pinfunction "2_2") (pintype "passive"))
    )
    (net (code "57") (name "Net-(R29-Pad2)") (class "Default")
      (node (ref "R29") (pin "2") (pinfunction "2_2") (pintype "passive"))
      (node (ref "R33") (pin "2") (pinfunction "2_2") (pintype "passive"))
      (node (ref "R34") (pin "1") (pinfunction "1_1") (pintype "passive"))
    )
    (net (code "58") (name "Net-(R30-Pad2)") (class "Default")
      (node (ref "R30") (pin "2") (pinfunction "2_2") (pintype "passive"))
      (node (ref "R34") (pin "2") (pinfunction "2_2") (pintype "passive"))
      (node (ref "R35") (pin "1") (pinfunction "1_1") (pintype "passive"))
    )
    (net (code "59") (name "Net-(R31-Pad2)") (class "Default")
      (node (ref "R31") (pin "2") (pinfunction "2_2") (pintype "passive"))
      (node (ref "R35") (pin "2") (pinfunction "2_2") (pintype "passive"))
      (node (ref "R36") (pin "1") (pinfunction "1_1") (pintype "passive"))
    )
    (net (code "60") (name "Net-(U2-BST)") (class "Default")
      (node (ref "C1") (pin "2") (pinfunction "2_2") (pintype "passive"))
      (node (ref "U2") (pin "6") (pinfunction "BST_6") (pintype "passive"))
    )
    (net (code "61") (name "Net-(U2-SW)") (class "Default")
      (node (ref "C1") (pin "1") (pinfunction "1_1") (pintype "passive"))
      (node (ref "L1") (pin "1") (pinfunction "1_1") (pintype "passive"))
      (node (ref "U2") (pin "5") (pinfunction "SW_5") (pintype "passive"))
    )
    (net (code "62") (name "VBUS") (class "Default")
      (node (ref "C2") (pin "2") (pinfunction "2_2") (pintype "passive"))
      (node (ref "C8") (pin "2") (pinfunction "2_2") (pintype "passive"))
      (node (ref "FB1") (pin "1") (pinfunction "1_1") (pintype "passive"))
      (node (ref "J1") (pin "A4_B9") (pinfunction "VBUS_A4_B9") (pintype "passive"))
      (node (ref "J1") (pin "B4_A9") (pinfunction "VBUS_B4_A9") (pintype "passive"))
      (node (ref "U3") (pin "5") (pinfunction "5_5") (pintype "passive"))
    )
    (net (code "63") (name "unconnected-(J1-SBU1-PadA8)") (class "Default")
      (node (ref "J1") (pin "A8") (pinfunction "SBU1_A8") (pintype "passive+no_connect"))
    )
    (net (code "64") (name "unconnected-(J1-SBU2-PadB8)") (class "Default")
      (node (ref "J1") (pin "B8") (pinfunction "SBU2_B8") (pintype "passive+no_connect"))
    )
    (net (code "65") (name "unconnected-(J2-Pad4)") (class "Default")
      (node (ref "J2") (pin "4") (pinfunction "4_4") (pintype "passive+no_connect"))
    )
    (net (code "66") (name "unconnected-(J2-Pad11)") (class "Default")
      (node (ref "J2") (pin "11") (pinfunction "11_11") (pintype "passive+no_connect"))
    )
    (net (code "67") (name "unconnected-(J2-Pad12)") (class "Default")
      (node (ref "J2") (pin "12") (pinfunction "12_12") (pintype "passive+no_connect"))
    )
    (net (code "68") (name "unconnected-(J2-Pad15)") (class "Default")
      (node (ref "J2") (pin "15") (pinfunction "15_15") (pintype "passive+no_connect"))
    )
    (net (code "69") (name "unconnected-(U1-IO39-Pad32)") (class "Default")
      (node (ref "U1") (pin "32") (pinfunction "IO39_32") (pintype "passive+no_connect"))
    )
    (net (code "70") (name "unconnected-(U1-IO40-Pad33)") (class "Default")
      (node (ref "U1") (pin "33") (pinfunction "IO40_33") (pintype "passive+no_connect"))
    )
    (net (code "71") (name "unconnected-(U1-IO41-Pad34)") (class "Default")
      (node (ref "U1") (pin "34") (pinfunction "IO41_34") (pintype "passive+no_connect"))
    )
    (net (code "72") (name "unconnected-(U1-IO42-Pad35)") (class "Default")
      (node (ref "U1") (pin "35") (pinfunction "IO42_35") (pintype "passive+no_connect"))
    )
    (net (code "73") (name "unconnected-(U1-IO45-Pad26)") (class "Default")
      (node (ref "U1") (pin "26") (pinfunction "IO45_26") (pintype "passive+no_connect"))
    )
  )
)
